# Detector.net
KiCad netlist of a schematic drawn in EasyEDA
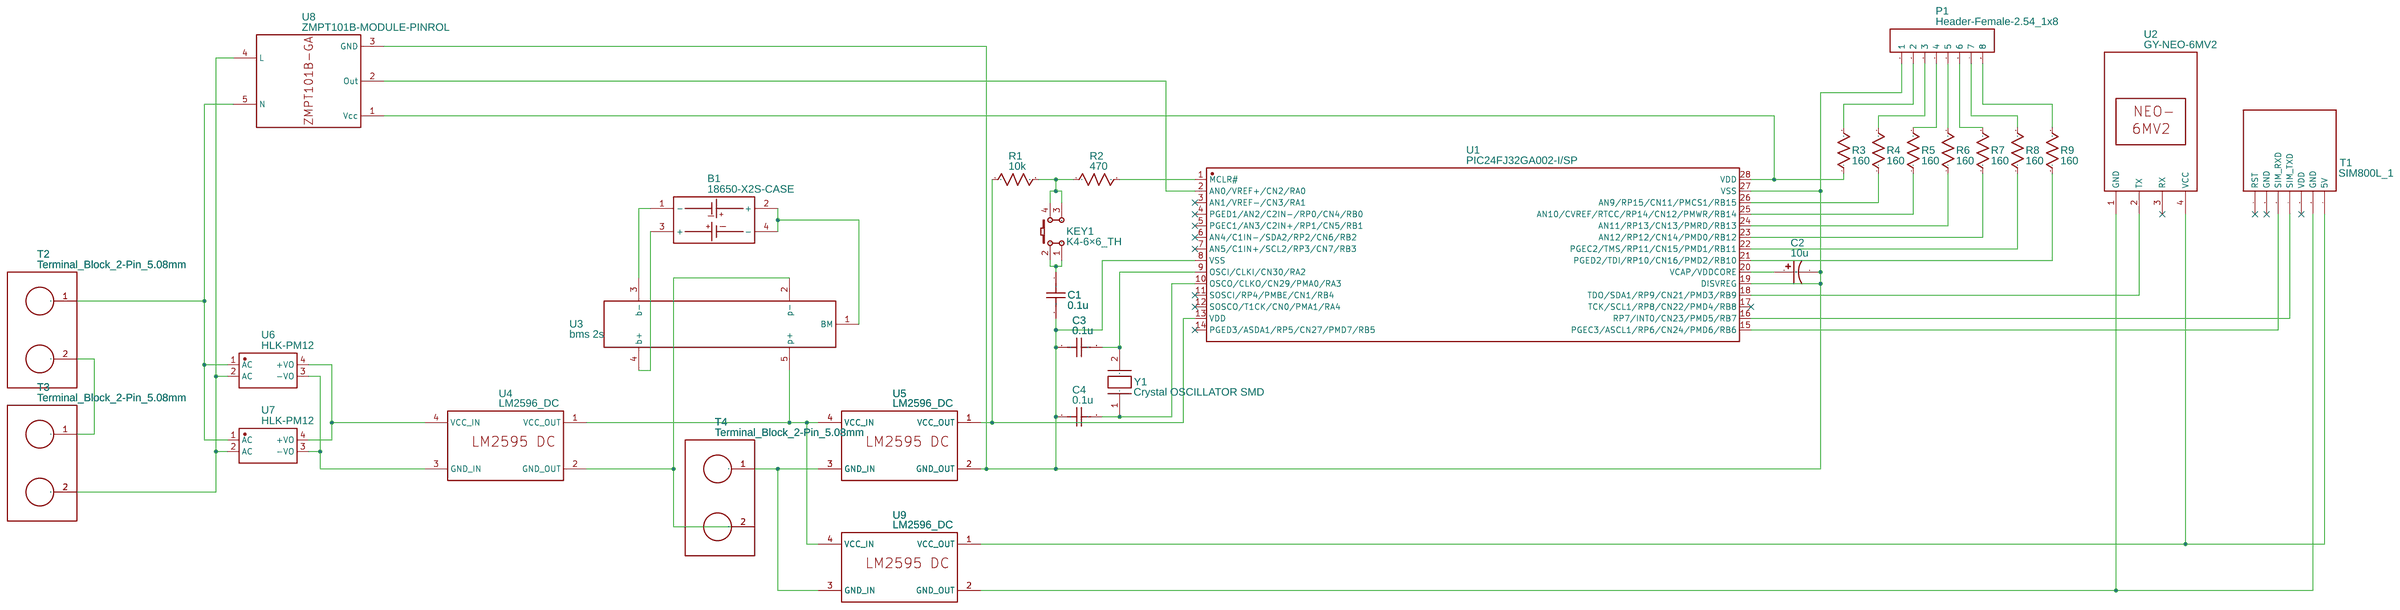
[diagram p0: schematic sheet]

(export (version "E")
  (design (tool "Eeschema 10.0.6"))
  (components
    (comp (ref "B1")
      (value "18650-X2S-CASE")
      (fields (field (name "BOM_Manufacturer Part") "18650-X2S"))
      (libsource (lib "") (part "18650-X2S-CASE"))
    )
    (comp (ref "C1") (value "0.1u") (libsource (lib "") (part "C_0603_US_1")))
    (comp (ref "C2") (value "10u") (libsource (lib "") (part "C_Tan_SMD_A_US")))
    (comp (ref "C3") (value "0.1u") (libsource (lib "") (part "C_0603_US")))
    (comp (ref "C4") (value "0.1u") (libsource (lib "") (part "C_0603_US")))
    (comp (ref "KEY1")
      (value "K4-6×6_TH")
      (fields
        (field (name "BOM_Manufacturer Part") "K2-1102DP-E4SW-04")
        (field (name "BOM_Supplier Part") "C136684")
      )
      (libsource (lib "") (part "K4-6×6_TH"))
    )
    (comp (ref "P1")
      (value "Header-Female-2.54_1x8")
      (fields
        (field (name "BOM_Manufacturer Part") "Female headerHDR1X8-2.54")
        (field (name "BOM_Supplier Part") "C27438")
      )
      (libsource (lib "") (part "Header-Female-2.54_1x8"))
    )
    (comp (ref "R1") (value "10k") (libsource (lib "") (part "R_0603_US_1")))
    (comp (ref "R2") (value "470") (libsource (lib "") (part "R_0603_US_1")))
    (comp (ref "R3") (value "160") (libsource (lib "") (part "R_0603_US")))
    (comp (ref "R4") (value "160") (libsource (lib "") (part "R_0603_US")))
    (comp (ref "R5") (value "160") (libsource (lib "") (part "R_0603_US")))
    (comp (ref "R6") (value "160") (libsource (lib "") (part "R_0603_US")))
    (comp (ref "R7") (value "160") (libsource (lib "") (part "R_0603_US")))
    (comp (ref "R8") (value "160") (libsource (lib "") (part "R_0603_US")))
    (comp (ref "R9") (value "160") (libsource (lib "") (part "R_0603_US")))
    (comp (ref "T1") (value "SIM800L_1") (libsource (lib "") (part "SIM800L_1")))
    (comp (ref "T2")
      (value "Terminal_Block_2-Pin_5.08mm")
      (fields (field (name "BOM_Supplier Part") "DR55-8-Pin-5.08mm"))
      (libsource (lib "") (part "Terminal_Block_2-Pin_5.08mm"))
    )
    (comp (ref "T3")
      (value "Terminal_Block_2-Pin_5.08mm")
      (fields (field (name "BOM_Supplier Part") "DR55-8-Pin-5.08mm"))
      (libsource (lib "") (part "Terminal_Block_2-Pin_5.08mm"))
    )
    (comp (ref "T4")
      (value "Terminal_Block_2-Pin_5.08mm")
      (fields (field (name "BOM_Supplier Part") "DR55-8-Pin-5.08mm"))
      (libsource (lib "") (part "Terminal_Block_2-Pin_5.08mm"))
    )
    (comp (ref "U1")
      (value "PIC24FJ32GA002-I/SP")
      (fields (field (name "BOM_Supplier Part") "C643615"))
      (libsource (lib "") (part "PIC24FJ32GA002-I/SP"))
    )
    (comp (ref "U2") (value "GY-NEO-6MV2") (libsource (lib "") (part "GY-NEO-6MV2")))
    (comp (ref "U3") (value "bms 2s") (libsource (lib "") (part "bms 2s")))
    (comp (ref "U4")
      (value "LM2596_DC")
      (fields (field (name "BOM_Manufacturer Part") "LM2596 DC 5V"))
      (libsource (lib "") (part "LM2596_DC"))
    )
    (comp (ref "U5")
      (value "LM2596_DC")
      (fields (field (name "BOM_Manufacturer Part") "LM2596 DC 5V"))
      (libsource (lib "") (part "LM2596_DC"))
    )
    (comp (ref "U6")
      (value "HLK-PM12")
      (fields (field (name "BOM_Supplier Part") "C209905"))
      (libsource (lib "") (part "HLK-PM12"))
    )
    (comp (ref "U7")
      (value "HLK-PM12")
      (fields (field (name "BOM_Supplier Part") "C209905"))
      (libsource (lib "") (part "HLK-PM12"))
    )
    (comp (ref "U8") (value "ZMPT101B-MODULE-PINROL") (libsource (lib "") (part "ZMPT101B-MODULE-PINROL")))
    (comp (ref "U9")
      (value "LM2596_DC")
      (fields (field (name "BOM_Manufacturer Part") "LM2596 DC 5V"))
      (libsource (lib "") (part "LM2596_DC"))
    )
    (comp (ref "Y1")
      (value "Crystal OSCILLATOR SMD")
      (fields
        (field (name "BOM_Manufacturer Part") "ABLS-4.000MHz-B2")
        (field (name "BOM_Supplier Part") "703-1777")
      )
      (libsource (lib "") (part "Crystal OSCILLATOR SMD"))
    )
  )
  (nets
    (net (code "1") (name "Net-(C1-Pad1)") (class "Default")
      (node (ref "C1") (pin "1") (pinfunction "1_1") (pintype "unspecified"))
      (node (ref "KEY1") (pin "1") (pinfunction "1_1") (pintype "unspecified"))
      (node (ref "KEY1") (pin "2") (pinfunction "2_2") (pintype "unspecified"))
    )
    (net (code "2") (name "Net-(KEY1-Pad3)") (class "Default")
      (node (ref "KEY1") (pin "3") (pinfunction "3_3") (pintype "unspecified"))
      (node (ref "KEY1") (pin "4") (pinfunction "4_4") (pintype "unspecified"))
      (node (ref "R1") (pin "2") (pinfunction "2_2") (pintype "unspecified"))
      (node (ref "R2") (pin "1") (pinfunction "1_1") (pintype "unspecified"))
    )
    (net (code "3") (name "Net-(P1-Pad2)") (class "Default")
      (node (ref "P1") (pin "2") (pinfunction "2_2") (pintype "input"))
      (node (ref "R3") (pin "2") (pinfunction "2_2") (pintype "unspecified"))
    )
    (net (code "4") (name "Net-(P1-Pad3)") (class "Default")
      (node (ref "P1") (pin "3") (pinfunction "3_3") (pintype "input"))
      (node (ref "R4") (pin "2") (pinfunction "2_2") (pintype "unspecified"))
    )
    (net (code "5") (name "Net-(P1-Pad4)") (class "Default")
      (node (ref "P1") (pin "4") (pinfunction "4_4") (pintype "input"))
      (node (ref "R5") (pin "2") (pinfunction "2_2") (pintype "unspecified"))
    )
    (net (code "6") (name "Net-(P1-Pad5)") (class "Default")
      (node (ref "P1") (pin "5") (pinfunction "5_5") (pintype "input"))
      (node (ref "R6") (pin "2") (pinfunction "2_2") (pintype "unspecified"))
    )
    (net (code "7") (name "Net-(P1-Pad6)") (class "Default")
      (node (ref "P1") (pin "6") (pinfunction "6_6") (pintype "input"))
      (node (ref "R7") (pin "2") (pinfunction "2_2") (pintype "unspecified"))
    )
    (net (code "8") (name "Net-(P1-Pad7)") (class "Default")
      (node (ref "P1") (pin "7") (pinfunction "7_7") (pintype "input"))
      (node (ref "R8") (pin "2") (pinfunction "2_2") (pintype "unspecified"))
    )
    (net (code "9") (name "Net-(P1-Pad8)") (class "Default")
      (node (ref "P1") (pin "8") (pinfunction "8_8") (pintype "input"))
      (node (ref "R9") (pin "2") (pinfunction "2_2") (pintype "unspecified"))
    )
    (net (code "10") (name "Net-(T1-5V)") (class "Default")
      (node (ref "T1") (pin "7") (pinfunction "5V_7") (pintype "unspecified"))
      (node (ref "U2") (pin "4") (pinfunction "VCC_4") (pintype "unspecified"))
      (node (ref "U9") (pin "1") (pinfunction "VCC_OUT_1") (pintype "unspecified"))
    )
    (net (code "11") (name "Net-(T1-SIM_RXD)") (class "Default")
      (node (ref "T1") (pin "3") (pinfunction "SIM_RXD_3") (pintype "unspecified"))
      (node (ref "U1") (pin "15") (pinfunction "PGEC3/ASCL1/RP6/CN24/PMD6/RB6_15") (pintype "unspecified"))
    )
    (net (code "12") (name "Net-(T1-SIM_TXD)") (class "Default")
      (node (ref "T1") (pin "4") (pinfunction "SIM_TXD_4") (pintype "unspecified"))
      (node (ref "U1") (pin "16") (pinfunction "RP7/INT0/CN23/PMD5/RB7_16") (pintype "unspecified"))
    )
    (net (code "13") (name "Net-(T2-Pad2)") (class "Default")
      (node (ref "T2") (pin "2") (pinfunction "2_2") (pintype "unspecified"))
      (node (ref "T3") (pin "1") (pinfunction "1_1") (pintype "unspecified"))
    )
    (net (code "14") (name "Net-(U1-AN0{slash}VREF+{slash}CN2{slash}RA0)") (class "Default")
      (node (ref "U1") (pin "2") (pinfunction "AN0/VREF+/CN2/RA0_2") (pintype "unspecified"))
      (node (ref "U8") (pin "2") (pinfunction "Out_2") (pintype "unspecified"))
    )
    (net (code "15") (name "Net-(U1-AN9{slash}RP15{slash}CN11{slash}PMCS1{slash}RB15)") (class "Default")
      (node (ref "R4") (pin "1") (pinfunction "1_1") (pintype "unspecified"))
      (node (ref "U1") (pin "26") (pinfunction "AN9/RP15/CN11/PMCS1/RB15_26") (pintype "unspecified"))
    )
    (net (code "16") (name "Net-(U1-AN10{slash}CVREF{slash}RTCC{slash}RP14{slash}CN12{slash}PMWR{slash}RB14)") (class "Default")
      (node (ref "R5") (pin "1") (pinfunction "1_1") (pintype "unspecified"))
      (node (ref "U1") (pin "25") (pinfunction "AN10/CVREF/RTCC/RP14/CN12/PMWR/RB14_25") (pintype "unspecified"))
    )
    (net (code "17") (name "Net-(U1-AN11{slash}RP13{slash}CN13{slash}PMRD{slash}RB13)") (class "Default")
      (node (ref "R6") (pin "1") (pinfunction "1_1") (pintype "unspecified"))
      (node (ref "U1") (pin "24") (pinfunction "AN11/RP13/CN13/PMRD/RB13_24") (pintype "unspecified"))
    )
    (net (code "18") (name "Net-(U1-AN12{slash}RP12{slash}CN14{slash}PMD0{slash}RB12)") (class "Default")
      (node (ref "R7") (pin "1") (pinfunction "1_1") (pintype "unspecified"))
      (node (ref "U1") (pin "23") (pinfunction "AN12/RP12/CN14/PMD0/RB12_23") (pintype "unspecified"))
    )
    (net (code "19") (name "Net-(U1-DISVREG)") (class "Default")
      (node (ref "C1") (pin "2") (pinfunction "2_2") (pintype "unspecified"))
      (node (ref "C2") (pin "2") (pinfunction "2_2") (pintype "unspecified"))
      (node (ref "C3") (pin "1") (pinfunction "1_1") (pintype "unspecified"))
      (node (ref "C4") (pin "1") (pinfunction "1_1") (pintype "unspecified"))
      (node (ref "P1") (pin "1") (pinfunction "1_1") (pintype "input"))
      (node (ref "U1") (pin "19") (pinfunction "DISVREG_19") (pintype "unspecified"))
      (node (ref "U1") (pin "27") (pinfunction "VSS_27") (pintype "unspecified"))
      (node (ref "U1") (pin "8") (pinfunction "VSS_8") (pintype "unspecified"))
      (node (ref "U5") (pin "2") (pinfunction "GND_OUT_2") (pintype "unspecified"))
      (node (ref "U8") (pin "3") (pinfunction "GND_3") (pintype "unspecified"))
    )
    (net (code "20") (name "Net-(U1-MCLR#)") (class "Default")
      (node (ref "R2") (pin "2") (pinfunction "2_2") (pintype "unspecified"))
      (node (ref "U1") (pin "1") (pinfunction "MCLR#_1") (pintype "unspecified"))
    )
    (net (code "21") (name "Net-(U1-OSCI{slash}CLKI{slash}CN30{slash}RA2)") (class "Default")
      (node (ref "C3") (pin "2") (pinfunction "2_2") (pintype "unspecified"))
      (node (ref "U1") (pin "9") (pinfunction "OSCI/CLKI/CN30/RA2_9") (pintype "unspecified"))
      (node (ref "Y1") (pin "2") (pinfunction "2_2") (pintype "unspecified"))
    )
    (net (code "22") (name "Net-(U1-OSCO{slash}CLKO{slash}CN29{slash}PMA0{slash}RA3)") (class "Default")
      (node (ref "C4") (pin "2") (pinfunction "2_2") (pintype "unspecified"))
      (node (ref "U1") (pin "10") (pinfunction "OSCO/CLKO/CN29/PMA0/RA3_10") (pintype "unspecified"))
      (node (ref "Y1") (pin "1") (pinfunction "1_1") (pintype "unspecified"))
    )
    (net (code "23") (name "Net-(U1-PGEC2{slash}TMS{slash}RP11{slash}CN15{slash}PMD1{slash}RB11)") (class "Default")
      (node (ref "R8") (pin "1") (pinfunction "1_1") (pintype "unspecified"))
      (node (ref "U1") (pin "22") (pinfunction "PGEC2/TMS/RP11/CN15/PMD1/RB11_22") (pintype "unspecified"))
    )
    (net (code "24") (name "Net-(U1-PGED2{slash}TDI{slash}RP10{slash}CN16{slash}PMD2{slash}RB10)") (class "Default")
      (node (ref "R9") (pin "1") (pinfunction "1_1") (pintype "unspecified"))
      (node (ref "U1") (pin "21") (pinfunction "PGED2/TDI/RP10/CN16/PMD2/RB10_21") (pintype "unspecified"))
    )
    (net (code "25") (name "Net-(U1-TDO{slash}SDA1{slash}RP9{slash}CN21{slash}PMD3{slash}RB9)") (class "Default")
      (node (ref "U1") (pin "18") (pinfunction "TDO/SDA1/RP9/CN21/PMD3/RB9_18") (pintype "unspecified"))
      (node (ref "U2") (pin "2") (pinfunction "TX_2") (pintype "unspecified"))
    )
    (net (code "26") (name "Net-(U1-VCAP{slash}VDDCORE)") (class "Default")
      (node (ref "C2") (pin "1") (pinfunction "1_1") (pintype "unspecified"))
      (node (ref "U1") (pin "20") (pinfunction "VCAP/VDDCORE_20") (pintype "unspecified"))
    )
    (net (code "27") (name "Net-(U2-GND)") (class "Default")
      (node (ref "T1") (pin "6") (pinfunction "GND_6") (pintype "unspecified"))
      (node (ref "U2") (pin "1") (pinfunction "GND_1") (pintype "unspecified"))
      (node (ref "U9") (pin "2") (pinfunction "GND_OUT_2") (pintype "unspecified"))
    )
    (net (code "28") (name "Net-(U3-BM)") (class "Default")
      (node (ref "B1") (pin "2") (pinfunction "+_2") (pintype "unspecified"))
      (node (ref "B1") (pin "4") (pinfunction "-_4") (pintype "unspecified"))
      (node (ref "U3") (pin "1") (pinfunction "BM_1") (pintype "unspecified"))
    )
    (net (code "29") (name "Net-(U3-b+)") (class "Default")
      (node (ref "B1") (pin "3") (pinfunction "+_3") (pintype "unspecified"))
      (node (ref "U3") (pin "4") (pinfunction "b+_4") (pintype "unspecified"))
    )
    (net (code "30") (name "Net-(U3-b-)") (class "Default")
      (node (ref "B1") (pin "1") (pinfunction "-_1") (pintype "unspecified"))
      (node (ref "U3") (pin "3") (pinfunction "b-_3") (pintype "unspecified"))
    )
    (net (code "31") (name "Net-(U3-p+)") (class "Default")
      (node (ref "U3") (pin "5") (pinfunction "p+_5") (pintype "unspecified"))
      (node (ref "U4") (pin "1") (pinfunction "VCC_OUT_1") (pintype "unspecified"))
      (node (ref "U5") (pin "4") (pinfunction "VCC_IN_4") (pintype "unspecified"))
      (node (ref "U9") (pin "4") (pinfunction "VCC_IN_4") (pintype "unspecified"))
    )
    (net (code "32") (name "Net-(U3-p-)") (class "Default")
      (node (ref "T4") (pin "2") (pinfunction "2_2") (pintype "unspecified"))
      (node (ref "U3") (pin "2") (pinfunction "p-_2") (pintype "unspecified"))
      (node (ref "U4") (pin "2") (pinfunction "GND_OUT_2") (pintype "unspecified"))
    )
    (net (code "33") (name "Net-(U4-GND_IN)") (class "Default")
      (node (ref "U4") (pin "3") (pinfunction "GND_IN_3") (pintype "unspecified"))
      (node (ref "U6") (pin "3") (pinfunction "-VO_3") (pintype "unspecified"))
      (node (ref "U7") (pin "3") (pinfunction "-VO_3") (pintype "unspecified"))
    )
    (net (code "34") (name "Net-(U4-VCC_IN)") (class "Default")
      (node (ref "U4") (pin "4") (pinfunction "VCC_IN_4") (pintype "unspecified"))
      (node (ref "U6") (pin "4") (pinfunction "+VO_4") (pintype "unspecified"))
      (node (ref "U7") (pin "4") (pinfunction "+VO_4") (pintype "unspecified"))
    )
    (net (code "35") (name "Net-(U5-GND_IN)") (class "Default")
      (node (ref "T4") (pin "1") (pinfunction "1_1") (pintype "unspecified"))
      (node (ref "U5") (pin "3") (pinfunction "GND_IN_3") (pintype "unspecified"))
      (node (ref "U9") (pin "3") (pinfunction "GND_IN_3") (pintype "unspecified"))
    )
    (net (code "36") (name "Net-(U5-VCC_OUT)") (class "Default")
      (node (ref "R1") (pin "1") (pinfunction "1_1") (pintype "unspecified"))
      (node (ref "U1") (pin "13") (pinfunction "VDD_13") (pintype "unspecified"))
      (node (ref "U5") (pin "1") (pinfunction "VCC_OUT_1") (pintype "unspecified"))
    )
    (net (code "37") (name "Net-(U8-L)") (class "Default")
      (node (ref "T3") (pin "2") (pinfunction "2_2") (pintype "unspecified"))
      (node (ref "U6") (pin "2") (pinfunction "AC_2") (pintype "unspecified"))
      (node (ref "U7") (pin "2") (pinfunction "AC_2") (pintype "unspecified"))
      (node (ref "U8") (pin "4") (pinfunction "L_4") (pintype "unspecified"))
    )
    (net (code "38") (name "Net-(U8-N)") (class "Default")
      (node (ref "T2") (pin "1") (pinfunction "1_1") (pintype "unspecified"))
      (node (ref "U6") (pin "1") (pinfunction "AC_1") (pintype "unspecified"))
      (node (ref "U7") (pin "1") (pinfunction "AC_1") (pintype "unspecified"))
      (node (ref "U8") (pin "5") (pinfunction "N_5") (pintype "unspecified"))
    )
    (net (code "39") (name "Net-(U8-Vcc)") (class "Default")
      (node (ref "R3") (pin "1") (pinfunction "1_1") (pintype "unspecified"))
      (node (ref "U1") (pin "28") (pinfunction "VDD_28") (pintype "unspecified"))
      (node (ref "U8") (pin "1") (pinfunction "Vcc_1") (pintype "unspecified"))
    )
    (net (code "40") (name "unconnected-(T1-GND-Pad2)") (class "Default")
      (node (ref "T1") (pin "2") (pinfunction "GND_2") (pintype "unspecified+no_connect"))
    )
    (net (code "41") (name "unconnected-(T1-RST-Pad1)") (class "Default")
      (node (ref "T1") (pin "1") (pinfunction "RST_1") (pintype "unspecified+no_connect"))
    )
    (net (code "42") (name "unconnected-(T1-VDD-Pad5)") (class "Default")
      (node (ref "T1") (pin "5") (pinfunction "VDD_5") (pintype "unspecified+no_connect"))
    )
    (net (code "43") (name "unconnected-(U1-AN1{slash}VREF-{slash}CN3{slash}RA1-Pad3)") (class "Default")
      (node (ref "U1") (pin "3") (pinfunction "AN1/VREF-/CN3/RA1_3") (pintype "unspecified+no_connect"))
    )
    (net (code "44") (name "unconnected-(U1-AN4{slash}C1IN-{slash}SDA2{slash}RP2{slash}CN6{slash}RB2-Pad6)") (class "Default")
      (node (ref "U1") (pin "6") (pinfunction "AN4/C1IN-/SDA2/RP2/CN6/RB2_6") (pintype "unspecified+no_connect"))
    )
    (net (code "45") (name "unconnected-(U1-AN5{slash}C1IN+{slash}SCL2{slash}RP3{slash}CN7{slash}RB3-Pad7)") (class "Default")
      (node (ref "U1") (pin "7") (pinfunction "AN5/C1IN+/SCL2/RP3/CN7/RB3_7") (pintype "unspecified+no_connect"))
    )
    (net (code "46") (name "unconnected-(U1-PGEC1{slash}AN3{slash}C2IN+{slash}RP1{slash}CN5{slash}RB1-Pad5)") (class "Default")
      (node (ref "U1") (pin "5") (pinfunction "PGEC1/AN3/C2IN+/RP1/CN5/RB1_5") (pintype "unspecified+no_connect"))
    )
    (net (code "47") (name "unconnected-(U1-PGED1{slash}AN2{slash}C2IN-{slash}RP0{slash}CN4{slash}RB0-Pad4)") (class "Default")
      (node (ref "U1") (pin "4") (pinfunction "PGED1/AN2/C2IN-/RP0/CN4/RB0_4") (pintype "unspecified+no_connect"))
    )
    (net (code "48") (name "unconnected-(U1-PGED3{slash}ASDA1{slash}RP5{slash}CN27{slash}PMD7{slash}RB5-Pad14)") (class "Default")
      (node (ref "U1") (pin "14") (pinfunction "PGED3/ASDA1/RP5/CN27/PMD7/RB5_14") (pintype "unspecified+no_connect"))
    )
    (net (code "49") (name "unconnected-(U1-SOSCI{slash}RP4{slash}PMBE{slash}CN1{slash}RB4-Pad11)") (class "Default")
      (node (ref "U1") (pin "11") (pinfunction "SOSCI/RP4/PMBE/CN1/RB4_11") (pintype "unspecified+no_connect"))
    )
    (net (code "50") (name "unconnected-(U1-SOSCO{slash}T1CK{slash}CN0{slash}PMA1{slash}RA4-Pad12)") (class "Default")
      (node (ref "U1") (pin "12") (pinfunction "SOSCO/T1CK/CN0/PMA1/RA4_12") (pintype "unspecified+no_connect"))
    )
    (net (code "51") (name "unconnected-(U1-TCK{slash}SCL1{slash}RP8{slash}CN22{slash}PMD4{slash}RB8-Pad17)") (class "Default")
      (node (ref "U1") (pin "17") (pinfunction "TCK/SCL1/RP8/CN22/PMD4/RB8_17") (pintype "unspecified+no_connect"))
    )
    (net (code "52") (name "unconnected-(U2-RX-Pad3)") (class "Default")
      (node (ref "U2") (pin "3") (pinfunction "RX_3") (pintype "unspecified+no_connect"))
    )
  )
)
